# licznik.net
KiCad netlist of a schematic drawn in EAGLE
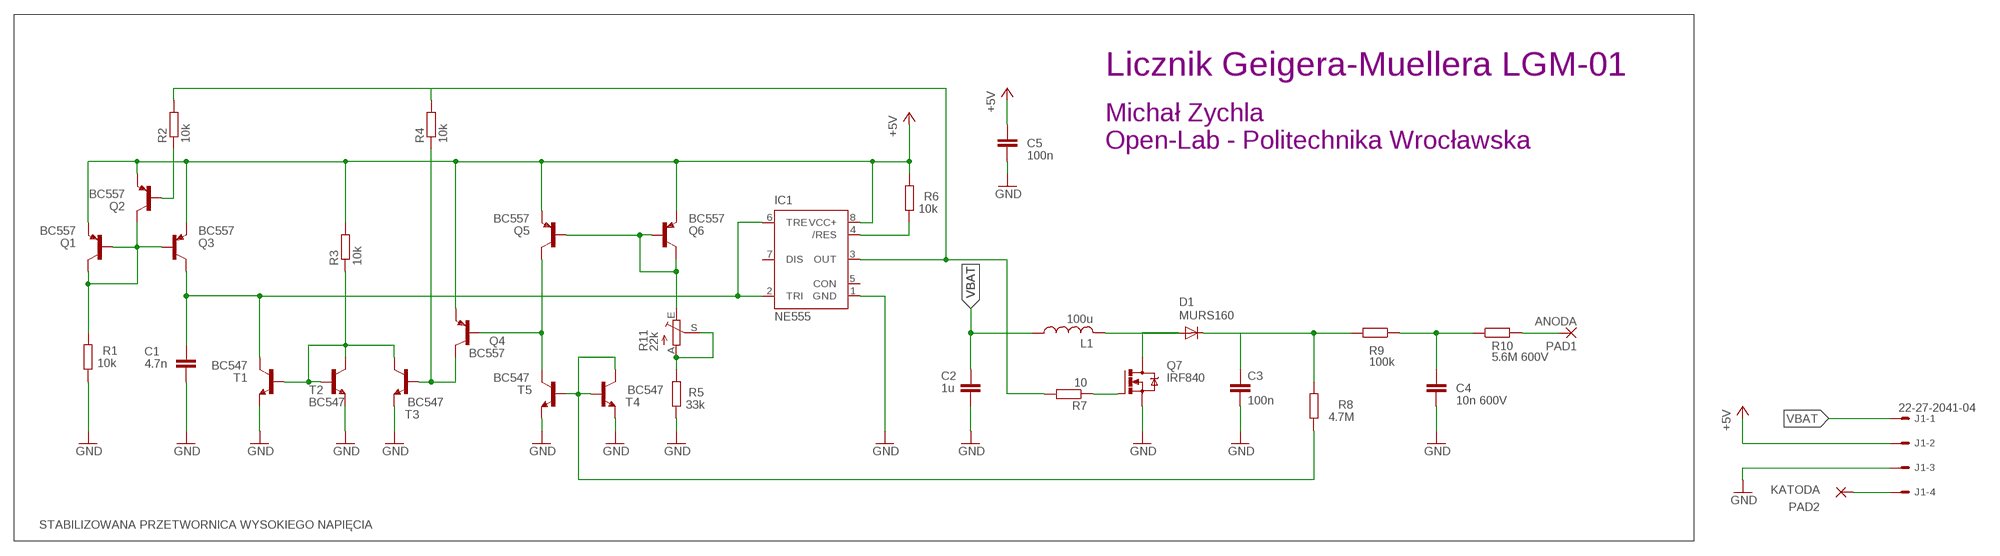
[diagram p0: schematic, sheet 1]

(export (version "E")
  (design (tool "Eeschema 10.0.6"))
  (components
    (comp (ref "C1")
      (value "4.7n")
      (footprint "eagle-import:C5B3")
      (libsource (lib "eagle-import") (part "C5/3"))
    )
    (comp (ref "C2")
      (value "1u")
      (footprint "eagle-import:C5B3")
      (libsource (lib "eagle-import") (part "C5/3"))
    )
    (comp (ref "C3")
      (value "100n")
      (footprint "eagle-import:C075-032X103")
      (libsource (lib "eagle-import") (part "C-EU075-032X103"))
    )
    (comp (ref "C4")
      (value "10n 600V")
      (footprint "eagle-import:C5B3")
      (libsource (lib "eagle-import") (part "C5/3"))
    )
    (comp (ref "C5")
      (value "100n")
      (footprint "eagle-import:C5B3")
      (libsource (lib "eagle-import") (part "C5/3"))
    )
    (comp (ref "D1")
      (value "MURS160")
      (footprint "eagle-import:SMB")
      (libsource (lib "eagle-import") (part "DIODE-SMB"))
    )
    (comp (ref "IC1")
      (value "NE555")
      (footprint "eagle-import:DIL-08")
      (fields (field (name "MF") "Arrow Electronics") (field (name "MPN") "NE555N"))
      (libsource (lib "eagle-import") (part "NE555"))
    )
    (comp (ref "J1")
      (value "22-27-2041-04")
      (footprint "eagle-import:6410-04")
      (libsource (lib "eagle-import") (part "22-?-0427-2041"))
    )
    (comp (ref "L1")
      (value "100u")
      (footprint "eagle-import:TJ3-U1")
      (libsource (lib "eagle-import") (part "L-USTJ3-U1"))
    )
    (comp (ref "PAD1")
      (value "ANODA")
      (footprint "eagle-import:2,15_1,0")
      (libsource (lib "eagle-import") (part "WIREPAD2,15/1,0"))
    )
    (comp (ref "PAD2")
      (value "KATODA")
      (footprint "eagle-import:2,15_1,0")
      (libsource (lib "eagle-import") (part "WIREPAD2,15/1,0"))
    )
    (comp (ref "Q1")
      (value "BC557")
      (footprint "eagle-import:TO92")
      (libsource (lib "eagle-import") (part "BC557"))
    )
    (comp (ref "Q2")
      (value "BC557")
      (footprint "eagle-import:TO92")
      (libsource (lib "eagle-import") (part "BC557"))
    )
    (comp (ref "Q3")
      (value "BC557")
      (footprint "eagle-import:TO92")
      (libsource (lib "eagle-import") (part "BC557"))
    )
    (comp (ref "Q4")
      (value "BC557")
      (footprint "eagle-import:TO92")
      (libsource (lib "eagle-import") (part "BC557"))
    )
    (comp (ref "Q5")
      (value "BC557")
      (footprint "eagle-import:TO92")
      (libsource (lib "eagle-import") (part "BC557"))
    )
    (comp (ref "Q6")
      (value "BC557")
      (footprint "eagle-import:TO92")
      (libsource (lib "eagle-import") (part "BC557"))
    )
    (comp (ref "Q7")
      (value "IRF840")
      (footprint "eagle-import:TO220BV")
      (libsource (lib "eagle-import") (part "IRF740"))
    )
    (comp (ref "R1")
      (value "10k")
      (footprint "eagle-import:0207_10")
      (libsource (lib "eagle-import") (part "R-EU_0207/10"))
    )
    (comp (ref "R2")
      (value "10k")
      (footprint "eagle-import:0207_10")
      (libsource (lib "eagle-import") (part "R-EU_0207/10"))
    )
    (comp (ref "R3")
      (value "10k")
      (footprint "eagle-import:0207_10")
      (libsource (lib "eagle-import") (part "R-EU_0207/10"))
    )
    (comp (ref "R4")
      (value "10k")
      (footprint "eagle-import:0207_10")
      (libsource (lib "eagle-import") (part "R-EU_0207/10"))
    )
    (comp (ref "R5")
      (value "33k")
      (footprint "eagle-import:0207_10")
      (libsource (lib "eagle-import") (part "R-EU_0207/10"))
    )
    (comp (ref "R6")
      (value "10k")
      (footprint "eagle-import:0207_10")
      (libsource (lib "eagle-import") (part "R-EU_0207/10"))
    )
    (comp (ref "R7")
      (value "10")
      (footprint "eagle-import:0207_10")
      (libsource (lib "eagle-import") (part "R-EU_0207/10"))
    )
    (comp (ref "R8")
      (value "4.7M")
      (footprint "eagle-import:0207_10")
      (libsource (lib "eagle-import") (part "R-EU_0207/10"))
    )
    (comp (ref "R9")
      (value "100k")
      (footprint "eagle-import:0207_10")
      (libsource (lib "eagle-import") (part "R-EU_0207/10"))
    )
    (comp (ref "R10")
      (value "5.6M 600V")
      (footprint "eagle-import:0411_12")
      (libsource (lib "eagle-import") (part "R-EU_0411/12"))
    )
    (comp (ref "R11")
      (value "22k")
      (footprint "eagle-import:CA6V")
      (libsource (lib "eagle-import") (part "TRIM_EU-CA6V"))
    )
    (comp (ref "T1")
      (value "BC547")
      (footprint "eagle-import:TO92")
      (libsource (lib "eagle-import") (part "BC547"))
    )
    (comp (ref "T2")
      (value "BC547")
      (footprint "eagle-import:TO92")
      (libsource (lib "eagle-import") (part "BC547"))
    )
    (comp (ref "T3")
      (value "BC547")
      (footprint "eagle-import:TO92")
      (libsource (lib "eagle-import") (part "BC547"))
    )
    (comp (ref "T4")
      (value "BC547")
      (footprint "eagle-import:TO92")
      (libsource (lib "eagle-import") (part "BC547"))
    )
    (comp (ref "T5")
      (value "BC547")
      (footprint "eagle-import:TO92")
      (libsource (lib "eagle-import") (part "BC547"))
    )
  )
  (nets
    (net (code "1") (name "+5V") (class "Default")
      (node (ref "C5") (pin "1") (pinfunction "1_1") (pintype "passive"))
      (node (ref "IC1") (pin "8") (pinfunction "VCC+_8") (pintype "power_in"))
      (node (ref "J1") (pin "2") (pinfunction "S_2") (pintype "passive"))
      (node (ref "Q1") (pin "1") (pinfunction "E_1") (pintype "passive"))
      (node (ref "Q2") (pin "1") (pinfunction "E_1") (pintype "passive"))
      (node (ref "Q3") (pin "1") (pinfunction "E_1") (pintype "passive"))
      (node (ref "Q4") (pin "1") (pinfunction "E_1") (pintype "passive"))
      (node (ref "Q5") (pin "1") (pinfunction "E_1") (pintype "passive"))
      (node (ref "Q6") (pin "1") (pinfunction "E_1") (pintype "passive"))
      (node (ref "R3") (pin "2") (pinfunction "2_2") (pintype "passive"))
      (node (ref "R6") (pin "2") (pinfunction "2_2") (pintype "passive"))
    )
    (net (code "2") (name "GND") (class "Default")
      (node (ref "C1") (pin "2") (pinfunction "2_2") (pintype "passive"))
      (node (ref "C2") (pin "2") (pinfunction "2_2") (pintype "passive"))
      (node (ref "C3") (pin "2") (pinfunction "2_2") (pintype "passive"))
      (node (ref "C4") (pin "2") (pinfunction "2_2") (pintype "passive"))
      (node (ref "C5") (pin "2") (pinfunction "2_2") (pintype "passive"))
      (node (ref "IC1") (pin "1") (pinfunction "GND_1") (pintype "power_in"))
      (node (ref "J1") (pin "3") (pinfunction "S_3") (pintype "passive"))
      (node (ref "Q7") (pin "S") (pinfunction "S_S") (pintype "passive"))
      (node (ref "R1") (pin "1") (pinfunction "1_1") (pintype "passive"))
      (node (ref "R5") (pin "1") (pinfunction "1_1") (pintype "passive"))
      (node (ref "T1") (pin "1") (pinfunction "E_1") (pintype "passive"))
      (node (ref "T2") (pin "1") (pinfunction "E_1") (pintype "passive"))
      (node (ref "T3") (pin "1") (pinfunction "E_1") (pintype "passive"))
      (node (ref "T4") (pin "1") (pinfunction "E_1") (pintype "passive"))
      (node (ref "T5") (pin "1") (pinfunction "E_1") (pintype "passive"))
    )
    (net (code "3") (name "Net-(C3-Pad1)") (class "Default")
      (node (ref "C3") (pin "1") (pinfunction "1_1") (pintype "passive"))
      (node (ref "D1") (pin "C") (pinfunction "C_C") (pintype "passive"))
      (node (ref "R8") (pin "2") (pinfunction "2_2") (pintype "passive"))
      (node (ref "R9") (pin "2") (pinfunction "2_2") (pintype "passive"))
    )
    (net (code "4") (name "Net-(C4-Pad1)") (class "Default")
      (node (ref "C4") (pin "1") (pinfunction "1_1") (pintype "passive"))
      (node (ref "R10") (pin "1") (pinfunction "1_1") (pintype "passive"))
      (node (ref "R9") (pin "1") (pinfunction "1_1") (pintype "passive"))
    )
    (net (code "5") (name "Net-(D1-PadA)") (class "Default")
      (node (ref "D1") (pin "A") (pinfunction "A_A") (pintype "passive"))
      (node (ref "L1") (pin "2") (pinfunction "2_2") (pintype "passive"))
      (node (ref "Q7") (pin "D") (pinfunction "D_D") (pintype "passive"))
    )
    (net (code "6") (name "Net-(IC1-OUT)") (class "Default")
      (node (ref "IC1") (pin "3") (pinfunction "OUT_3") (pintype "output"))
      (node (ref "R2") (pin "2") (pinfunction "2_2") (pintype "passive"))
      (node (ref "R4") (pin "2") (pinfunction "2_2") (pintype "passive"))
      (node (ref "R7") (pin "2") (pinfunction "2_2") (pintype "passive"))
    )
    (net (code "7") (name "Net-(IC1-TRE)") (class "Default")
      (node (ref "C1") (pin "1") (pinfunction "1_1") (pintype "passive"))
      (node (ref "IC1") (pin "2") (pinfunction "TRI_2") (pintype "input"))
      (node (ref "IC1") (pin "6") (pinfunction "TRE_6") (pintype "input"))
      (node (ref "Q3") (pin "3") (pinfunction "C_3") (pintype "passive"))
      (node (ref "T1") (pin "3") (pinfunction "C_3") (pintype "passive"))
    )
    (net (code "8") (name "Net-(IC1-{slash}RES)") (class "Default")
      (node (ref "IC1") (pin "4") (pinfunction "/RES_4") (pintype "input"))
      (node (ref "R6") (pin "1") (pinfunction "1_1") (pintype "passive"))
    )
    (net (code "9") (name "Net-(J1D-S)") (class "Default")
      (node (ref "J1") (pin "4") (pinfunction "S_4") (pintype "passive"))
      (node (ref "PAD2") (pin "1") (pinfunction "P_1") (pintype "passive"))
    )
    (net (code "10") (name "Net-(PAD1-P)") (class "Default")
      (node (ref "PAD1") (pin "1") (pinfunction "P_1") (pintype "passive"))
      (node (ref "R10") (pin "2") (pinfunction "2_2") (pintype "passive"))
    )
    (net (code "11") (name "Net-(Q1-B)") (class "Default")
      (node (ref "Q1") (pin "2") (pinfunction "B_2") (pintype "passive"))
      (node (ref "Q1") (pin "3") (pinfunction "C_3") (pintype "passive"))
      (node (ref "Q2") (pin "3") (pinfunction "C_3") (pintype "passive"))
      (node (ref "Q3") (pin "2") (pinfunction "B_2") (pintype "passive"))
      (node (ref "R1") (pin "2") (pinfunction "2_2") (pintype "passive"))
    )
    (net (code "12") (name "Net-(Q2-B)") (class "Default")
      (node (ref "Q2") (pin "2") (pinfunction "B_2") (pintype "passive"))
      (node (ref "R2") (pin "1") (pinfunction "1_1") (pintype "passive"))
    )
    (net (code "13") (name "Net-(Q4-B)") (class "Default")
      (node (ref "Q4") (pin "2") (pinfunction "B_2") (pintype "passive"))
      (node (ref "Q5") (pin "3") (pinfunction "C_3") (pintype "passive"))
      (node (ref "T4") (pin "3") (pinfunction "C_3") (pintype "passive"))
    )
    (net (code "14") (name "Net-(Q4-C)") (class "Default")
      (node (ref "Q4") (pin "3") (pinfunction "C_3") (pintype "passive"))
      (node (ref "R4") (pin "1") (pinfunction "1_1") (pintype "passive"))
      (node (ref "T3") (pin "2") (pinfunction "B_2") (pintype "passive"))
    )
    (net (code "15") (name "Net-(Q5-B)") (class "Default")
      (node (ref "Q5") (pin "2") (pinfunction "B_2") (pintype "passive"))
      (node (ref "Q6") (pin "2") (pinfunction "B_2") (pintype "passive"))
      (node (ref "Q6") (pin "3") (pinfunction "C_3") (pintype "passive"))
      (node (ref "R11") (pin "E") (pinfunction "E_E") (pintype "passive"))
    )
    (net (code "16") (name "Net-(Q7-PadG)") (class "Default")
      (node (ref "Q7") (pin "G") (pinfunction "G_G") (pintype "passive"))
      (node (ref "R7") (pin "1") (pinfunction "1_1") (pintype "passive"))
    )
    (net (code "17") (name "Net-(R11-PadA)") (class "Default")
      (node (ref "R11") (pin "A") (pinfunction "A_A") (pintype "passive"))
      (node (ref "R11") (pin "S") (pinfunction "S_S") (pintype "passive"))
      (node (ref "R5") (pin "2") (pinfunction "2_2") (pintype "passive"))
    )
    (net (code "18") (name "Net-(T1-B)") (class "Default")
      (node (ref "R3") (pin "1") (pinfunction "1_1") (pintype "passive"))
      (node (ref "T1") (pin "2") (pinfunction "B_2") (pintype "passive"))
      (node (ref "T2") (pin "2") (pinfunction "B_2") (pintype "passive"))
      (node (ref "T2") (pin "3") (pinfunction "C_3") (pintype "passive"))
      (node (ref "T3") (pin "3") (pinfunction "C_3") (pintype "passive"))
    )
    (net (code "19") (name "Net-(T4-B)") (class "Default")
      (node (ref "R8") (pin "1") (pinfunction "1_1") (pintype "passive"))
      (node (ref "T4") (pin "2") (pinfunction "B_2") (pintype "passive"))
      (node (ref "T5") (pin "2") (pinfunction "B_2") (pintype "passive"))
      (node (ref "T5") (pin "3") (pinfunction "C_3") (pintype "passive"))
    )
    (net (code "20") (name "VBAT") (class "Default")
      (node (ref "C2") (pin "1") (pinfunction "1_1") (pintype "passive"))
      (node (ref "J1") (pin "1") (pinfunction "S_1") (pintype "passive"))
      (node (ref "L1") (pin "1") (pinfunction "1_1") (pintype "passive"))
    )
    (net (code "21") (name "unconnected-(IC1-CON-Pad5)") (class "Default")
      (node (ref "IC1") (pin "5") (pinfunction "CON_5") (pintype "input"))
    )
    (net (code "22") (name "unconnected-(IC1-DIS-Pad7)") (class "Default")
      (node (ref "IC1") (pin "7") (pinfunction "DIS_7") (pintype "input"))
    )
  )
)
